# Sheet1.net
KiCad netlist of a schematic drawn in Altium Designer
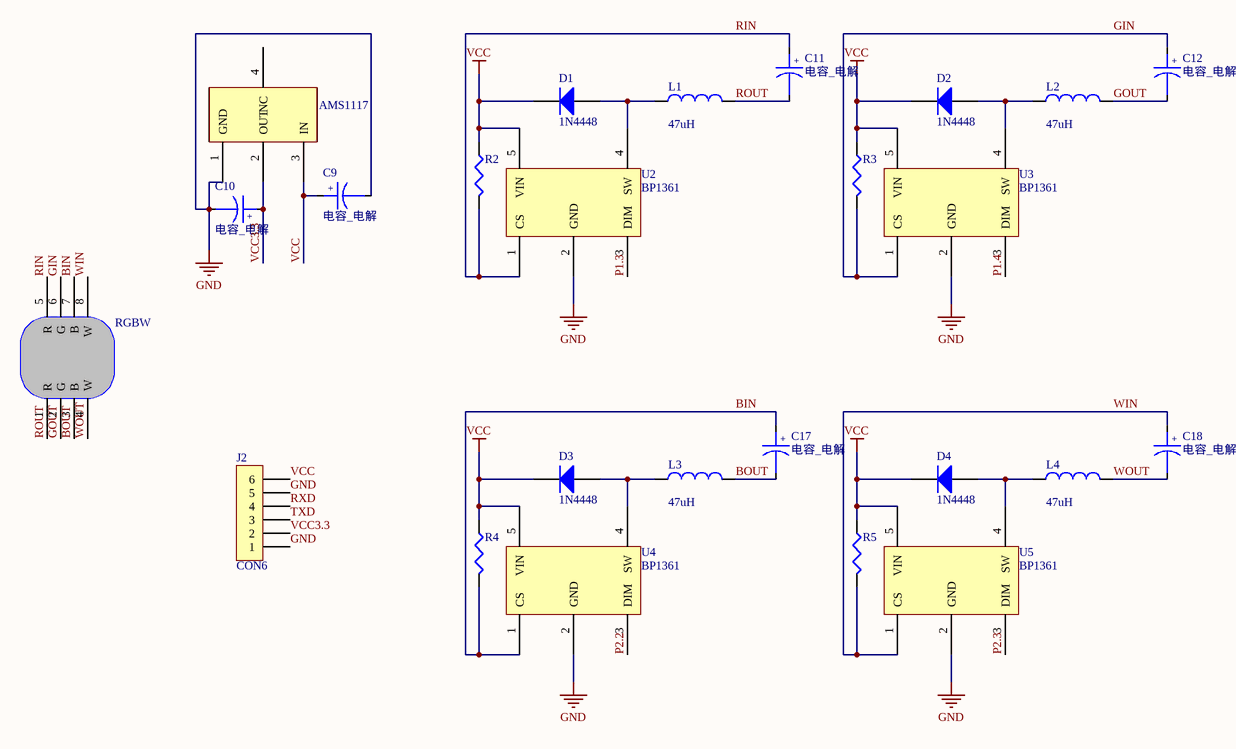
[diagram p0: Sheet1.SchDoc]

(export (version "E")
  (design (tool "Eeschema 10.0.6"))
  (components
    (comp (ref "AMS1117")
      (value "AMS1117")
      (footprint "SOT223")
      (libsource (lib "AMS1117") (part "Component_1"))
    )
    (comp (ref "C9")
      (value "电容_电解")
      (footprint "10UF")
      (description "Capacitor")
      (libsource (lib "基础元件") (part "电容_电解"))
    )
    (comp (ref "C10")
      (value "电容_电解")
      (footprint "10UF")
      (description "Capacitor")
      (libsource (lib "基础元件") (part "电容_电解"))
    )
    (comp (ref "C11")
      (value "电容_电解")
      (footprint "10UF")
      (description "Capacitor")
      (libsource (lib "基础元件") (part "电容_电解"))
    )
    (comp (ref "C12")
      (value "电容_电解")
      (footprint "10UF")
      (description "Capacitor")
      (libsource (lib "基础元件") (part "电容_电解"))
    )
    (comp (ref "C17")
      (value "电容_电解")
      (footprint "10UF")
      (description "Capacitor")
      (libsource (lib "基础元件") (part "电容_电解"))
    )
    (comp (ref "C18")
      (value "电容_电解")
      (footprint "10UF")
      (description "Capacitor")
      (libsource (lib "基础元件") (part "电容_电解"))
    )
    (comp (ref "D1")
      (value "1N4448")
      (footprint "DO-35")
      (description "High Conductance Fast Diode")
      (fields (field (name "PUBLISHER") "Altium Limited"))
      (libsource (lib "Miscellaneous Devices") (part "Diode 1N4448"))
    )
    (comp (ref "D2")
      (value "1N4448")
      (footprint "DO-35")
      (description "High Conductance Fast Diode")
      (fields (field (name "PUBLISHER") "Altium Limited"))
      (libsource (lib "Miscellaneous Devices") (part "Diode 1N4448"))
    )
    (comp (ref "D3")
      (value "1N4448")
      (footprint "DO-35")
      (description "High Conductance Fast Diode")
      (fields (field (name "PUBLISHER") "Altium Limited"))
      (libsource (lib "Miscellaneous Devices") (part "Diode 1N4448"))
    )
    (comp (ref "D4")
      (value "1N4448")
      (footprint "DO-35")
      (description "High Conductance Fast Diode")
      (fields (field (name "PUBLISHER") "Altium Limited"))
      (libsource (lib "Miscellaneous Devices") (part "Diode 1N4448"))
    )
    (comp (ref "J2")
      (value "CON6")
      (footprint "HDR1X6")
      (description "Connector")
      (libsource (lib "插针系列") (part "CON6"))
    )
    (comp (ref "L1")
      (value "47uH")
      (footprint "AXIAL0.4_10mm")
      (description "Inductor")
      (fields (field (name "PUBLISHER") "Altium Limited"))
      (libsource (lib "Miscellaneous Devices") (part "Inductor"))
    )
    (comp (ref "L2")
      (value "47uH")
      (footprint "AXIAL0.4_10mm")
      (description "Inductor")
      (fields (field (name "PUBLISHER") "Altium Limited"))
      (libsource (lib "Miscellaneous Devices") (part "Inductor"))
    )
    (comp (ref "L3")
      (value "47uH")
      (footprint "AXIAL0.4_10mm")
      (description "Inductor")
      (fields (field (name "PUBLISHER") "Altium Limited"))
      (libsource (lib "Miscellaneous Devices") (part "Inductor"))
    )
    (comp (ref "L4")
      (value "47uH")
      (footprint "AXIAL0.4_10mm")
      (description "Inductor")
      (fields (field (name "PUBLISHER") "Altium Limited"))
      (libsource (lib "Miscellaneous Devices") (part "Inductor"))
    )
    (comp (ref "R2")
      (value "RES")
      (footprint "2512")
      (description "Resistor")
      (libsource (lib "基础元件") (part "RES"))
    )
    (comp (ref "R3")
      (value "RES")
      (footprint "2512")
      (description "Resistor")
      (libsource (lib "基础元件") (part "RES"))
    )
    (comp (ref "R4")
      (value "RES")
      (footprint "2512")
      (description "Resistor")
      (libsource (lib "基础元件") (part "RES"))
    )
    (comp (ref "R5")
      (value "RES")
      (footprint "2512")
      (description "Resistor")
      (libsource (lib "基础元件") (part "RES"))
    )
    (comp (ref "RGBW")
      (value "Component_1")
      (footprint "RGBWLED")
      (libsource (lib "RGBWLED") (part "Component_1"))
    )
    (comp (ref "U2") (value "BP1361") (footprint "BSP1361") (libsource (lib "BP1361") (part "Component_1")))
    (comp (ref "U3") (value "BP1361") (footprint "BSP1361") (libsource (lib "BP1361") (part "Component_1")))
    (comp (ref "U4") (value "BP1361") (footprint "BSP1361") (libsource (lib "BP1361") (part "Component_1")))
    (comp (ref "U5") (value "BP1361") (footprint "BSP1361") (libsource (lib "BP1361") (part "Component_1")))
  )
  (nets
    (net (code "1") (name "/BIN") (class "Default")
      (node (ref "C17") (pin "1") (pinfunction "1_1") (pintype "passive"))
      (node (ref "R4") (pin "1") (pinfunction "TOP_1") (pintype "passive"))
      (node (ref "RGBW") (pin "7") (pinfunction "B_7") (pintype "passive"))
      (node (ref "U4") (pin "1") (pinfunction "CS_1") (pintype "passive"))
    )
    (net (code "2") (name "/BOUT") (class "Default")
      (node (ref "C17") (pin "2") (pinfunction "5_2") (pintype "passive"))
      (node (ref "L3") (pin "2") (pinfunction "2_2") (pintype "passive"))
      (node (ref "RGBW") (pin "3") (pinfunction "B_3") (pintype "passive"))
    )
    (net (code "3") (name "/GIN") (class "Default")
      (node (ref "C12") (pin "1") (pinfunction "1_1") (pintype "passive"))
      (node (ref "R3") (pin "1") (pinfunction "TOP_1") (pintype "passive"))
      (node (ref "RGBW") (pin "6") (pinfunction "G_6") (pintype "passive"))
      (node (ref "U3") (pin "1") (pinfunction "CS_1") (pintype "passive"))
    )
    (net (code "4") (name "/GOUT") (class "Default")
      (node (ref "C12") (pin "2") (pinfunction "5_2") (pintype "passive"))
      (node (ref "L2") (pin "2") (pinfunction "2_2") (pintype "passive"))
      (node (ref "RGBW") (pin "2") (pinfunction "G_2") (pintype "passive"))
    )
    (net (code "5") (name "/P1.3") (class "Default")
      (node (ref "U2") (pin "3") (pinfunction "DIM_3") (pintype "passive"))
    )
    (net (code "6") (name "/P1.4") (class "Default")
      (node (ref "U3") (pin "3") (pinfunction "DIM_3") (pintype "passive"))
    )
    (net (code "7") (name "/P2.2") (class "Default")
      (node (ref "U4") (pin "3") (pinfunction "DIM_3") (pintype "passive"))
    )
    (net (code "8") (name "/P2.3") (class "Default")
      (node (ref "U5") (pin "3") (pinfunction "DIM_3") (pintype "passive"))
    )
    (net (code "9") (name "/RIN") (class "Default")
      (node (ref "C11") (pin "1") (pinfunction "1_1") (pintype "passive"))
      (node (ref "R2") (pin "1") (pinfunction "TOP_1") (pintype "passive"))
      (node (ref "RGBW") (pin "5") (pinfunction "R_5") (pintype "passive"))
      (node (ref "U2") (pin "1") (pinfunction "CS_1") (pintype "passive"))
    )
    (net (code "10") (name "/ROUT") (class "Default")
      (node (ref "C11") (pin "2") (pinfunction "5_2") (pintype "passive"))
      (node (ref "L1") (pin "2") (pinfunction "2_2") (pintype "passive"))
      (node (ref "RGBW") (pin "1") (pinfunction "R_1") (pintype "passive"))
    )
    (net (code "11") (name "/RXD") (class "Default")
      (node (ref "J2") (pin "4") (pinfunction "4_4") (pintype "passive"))
    )
    (net (code "12") (name "/TXD") (class "Default")
      (node (ref "J2") (pin "3") (pinfunction "3_3") (pintype "passive"))
    )
    (net (code "13") (name "/VCC3.3") (class "Default")
      (node (ref "AMS1117") (pin "2") (pinfunction "OUT_2") (pintype "passive"))
      (node (ref "C10") (pin "1") (pinfunction "1_1") (pintype "passive"))
      (node (ref "J2") (pin "2") (pinfunction "2_2") (pintype "passive"))
    )
    (net (code "14") (name "/WIN") (class "Default")
      (node (ref "C18") (pin "1") (pinfunction "1_1") (pintype "passive"))
      (node (ref "R5") (pin "1") (pinfunction "TOP_1") (pintype "passive"))
      (node (ref "RGBW") (pin "8") (pinfunction "W_8") (pintype "passive"))
      (node (ref "U5") (pin "1") (pinfunction "CS_1") (pintype "passive"))
    )
    (net (code "15") (name "/WOUT") (class "Default")
      (node (ref "C18") (pin "2") (pinfunction "5_2") (pintype "passive"))
      (node (ref "L4") (pin "2") (pinfunction "2_2") (pintype "passive"))
      (node (ref "RGBW") (pin "4") (pinfunction "W_4") (pintype "passive"))
    )
    (net (code "16") (name "GND") (class "Default")
      (node (ref "AMS1117") (pin "1") (pinfunction "GND_1") (pintype "passive"))
      (node (ref "C10") (pin "2") (pinfunction "5_2") (pintype "passive"))
      (node (ref "C9") (pin "2") (pinfunction "5_2") (pintype "passive"))
      (node (ref "J2") (pin "1") (pinfunction "1_1") (pintype "passive"))
      (node (ref "J2") (pin "5") (pinfunction "5_5") (pintype "passive"))
      (node (ref "U2") (pin "2") (pinfunction "GND_2") (pintype "passive"))
      (node (ref "U3") (pin "2") (pinfunction "GND_2") (pintype "passive"))
      (node (ref "U4") (pin "2") (pinfunction "GND_2") (pintype "passive"))
      (node (ref "U5") (pin "2") (pinfunction "GND_2") (pintype "passive"))
    )
    (net (code "17") (name "Net-(D1-A)") (class "Default")
      (node (ref "D1") (pin "1") (pinfunction "A_1") (pintype "passive"))
      (node (ref "L1") (pin "1") (pinfunction "1_1") (pintype "passive"))
      (node (ref "U2") (pin "4") (pinfunction "SW_4") (pintype "passive"))
    )
    (net (code "18") (name "Net-(D2-A)") (class "Default")
      (node (ref "D2") (pin "1") (pinfunction "A_1") (pintype "passive"))
      (node (ref "L2") (pin "1") (pinfunction "1_1") (pintype "passive"))
      (node (ref "U3") (pin "4") (pinfunction "SW_4") (pintype "passive"))
    )
    (net (code "19") (name "Net-(D3-A)") (class "Default")
      (node (ref "D3") (pin "1") (pinfunction "A_1") (pintype "passive"))
      (node (ref "L3") (pin "1") (pinfunction "1_1") (pintype "passive"))
      (node (ref "U4") (pin "4") (pinfunction "SW_4") (pintype "passive"))
    )
    (net (code "20") (name "Net-(D4-A)") (class "Default")
      (node (ref "D4") (pin "1") (pinfunction "A_1") (pintype "passive"))
      (node (ref "L4") (pin "1") (pinfunction "1_1") (pintype "passive"))
      (node (ref "U5") (pin "4") (pinfunction "SW_4") (pintype "passive"))
    )
    (net (code "21") (name "VCC") (class "Default")
      (node (ref "AMS1117") (pin "3") (pinfunction "IN_3") (pintype "passive"))
      (node (ref "C9") (pin "1") (pinfunction "1_1") (pintype "passive"))
      (node (ref "D1") (pin "2") (pinfunction "K_2") (pintype "passive"))
      (node (ref "D2") (pin "2") (pinfunction "K_2") (pintype "passive"))
      (node (ref "D3") (pin "2") (pinfunction "K_2") (pintype "passive"))
      (node (ref "D4") (pin "2") (pinfunction "K_2") (pintype "passive"))
      (node (ref "J2") (pin "6") (pinfunction "6_6") (pintype "passive"))
      (node (ref "R2") (pin "2") (pinfunction "BOT_2") (pintype "passive"))
      (node (ref "R3") (pin "2") (pinfunction "BOT_2") (pintype "passive"))
      (node (ref "R4") (pin "2") (pinfunction "BOT_2") (pintype "passive"))
      (node (ref "R5") (pin "2") (pinfunction "BOT_2") (pintype "passive"))
      (node (ref "U2") (pin "5") (pinfunction "VIN_5") (pintype "passive"))
      (node (ref "U3") (pin "5") (pinfunction "VIN_5") (pintype "passive"))
      (node (ref "U4") (pin "5") (pinfunction "VIN_5") (pintype "passive"))
      (node (ref "U5") (pin "5") (pinfunction "VIN_5") (pintype "passive"))
    )
    (net (code "22") (name "unconnected-(AMS1117-NC-Pad4)") (class "Default")
      (node (ref "AMS1117") (pin "4") (pinfunction "NC_4") (pintype "passive"))
    )
  )
)
